# 5v_dc.net
KiCad netlist of a schematic drawn in EAGLE
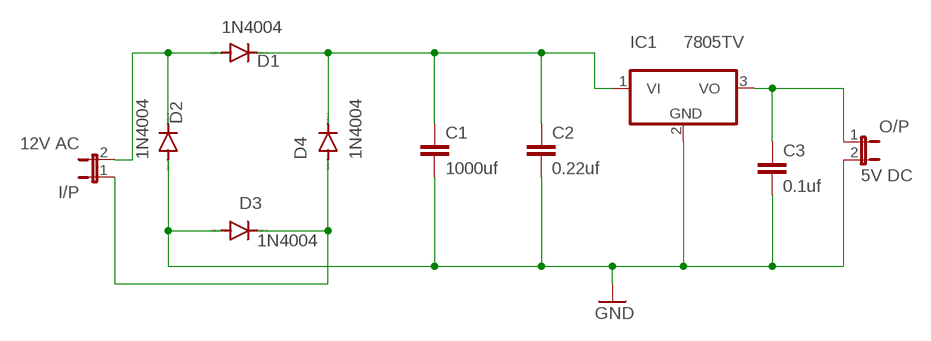
[diagram p0: schematic, sheet 1]

(export (version "E")
  (design (tool "Eeschema 10.0.6"))
  (components
    (comp (ref "C1")
      (value "1000uf")
      (footprint "eagle-import:C2.5-3")
      (libsource (lib "eagle-import") (part "C2,5-3"))
    )
    (comp (ref "C2")
      (value "0.22uf")
      (footprint "eagle-import:C2.5-3")
      (libsource (lib "eagle-import") (part "C2,5-3"))
    )
    (comp (ref "C3")
      (value "0.1uf")
      (footprint "eagle-import:C2.5-3")
      (libsource (lib "eagle-import") (part "C2,5-3"))
    )
    (comp (ref "D1")
      (value "1N4004")
      (footprint "eagle-import:DO41-10")
      (libsource (lib "eagle-import") (part "1N4004"))
    )
    (comp (ref "D2")
      (value "1N4004")
      (footprint "eagle-import:DO41-10")
      (libsource (lib "eagle-import") (part "1N4004"))
    )
    (comp (ref "D3")
      (value "1N4004")
      (footprint "eagle-import:DO41-10")
      (libsource (lib "eagle-import") (part "1N4004"))
    )
    (comp (ref "D4")
      (value "1N4004")
      (footprint "eagle-import:DO41-10")
      (libsource (lib "eagle-import") (part "1N4004"))
    )
    (comp (ref "I/P")
      (value "12V AC")
      (footprint "eagle-import:JP1")
      (libsource (lib "eagle-import") (part "JP1E"))
    )
    (comp (ref "IC1")
      (value "7805TV")
      (footprint "eagle-import:TO220V")
      (libsource (lib "eagle-import") (part "78TV05"))
    )
    (comp (ref "O/P")
      (value "5V DC")
      (footprint "eagle-import:JP1")
      (libsource (lib "eagle-import") (part "JP1E"))
    )
  )
  (nets
    (net (code "1") (name "GND") (class "Default")
      (node (ref "C1") (pin "2") (pinfunction "2_2") (pintype "passive"))
      (node (ref "C2") (pin "2") (pinfunction "2_2") (pintype "passive"))
      (node (ref "C3") (pin "2") (pinfunction "2_2") (pintype "passive"))
      (node (ref "D2") (pin "A") (pinfunction "A_A") (pintype "passive"))
      (node (ref "D3") (pin "A") (pinfunction "A_A") (pintype "passive"))
      (node (ref "IC1") (pin "2") (pinfunction "GND_2") (pintype "passive"))
      (node (ref "O/P") (pin "2") (pinfunction "2_2") (pintype "passive"))
    )
    (net (code "2") (name "Net-(D1-PadA)") (class "Default")
      (node (ref "D1") (pin "A") (pinfunction "A_A") (pintype "passive"))
      (node (ref "D2") (pin "C") (pinfunction "C_C") (pintype "passive"))
      (node (ref "I/P") (pin "2") (pinfunction "2_2") (pintype "passive"))
    )
    (net (code "3") (name "Net-(D3-PadC)") (class "Default")
      (node (ref "D3") (pin "C") (pinfunction "C_C") (pintype "passive"))
      (node (ref "D4") (pin "A") (pinfunction "A_A") (pintype "passive"))
      (node (ref "I/P") (pin "1") (pinfunction "1_1") (pintype "passive"))
    )
    (net (code "4") (name "Net-(IC1-VI)") (class "Default")
      (node (ref "C1") (pin "1") (pinfunction "1_1") (pintype "passive"))
      (node (ref "C2") (pin "1") (pinfunction "1_1") (pintype "passive"))
      (node (ref "D1") (pin "C") (pinfunction "C_C") (pintype "passive"))
      (node (ref "D4") (pin "C") (pinfunction "C_C") (pintype "passive"))
      (node (ref "IC1") (pin "1") (pinfunction "VI_1") (pintype "input"))
    )
    (net (code "5") (name "Net-(IC1-VO)") (class "Default")
      (node (ref "C3") (pin "1") (pinfunction "1_1") (pintype "passive"))
      (node (ref "IC1") (pin "3") (pinfunction "VO_3") (pintype "passive"))
      (node (ref "O/P") (pin "1") (pinfunction "1_1") (pintype "passive"))
    )
  )
)
